# Sheet1.net
KiCad netlist of a schematic drawn in Altium Designer
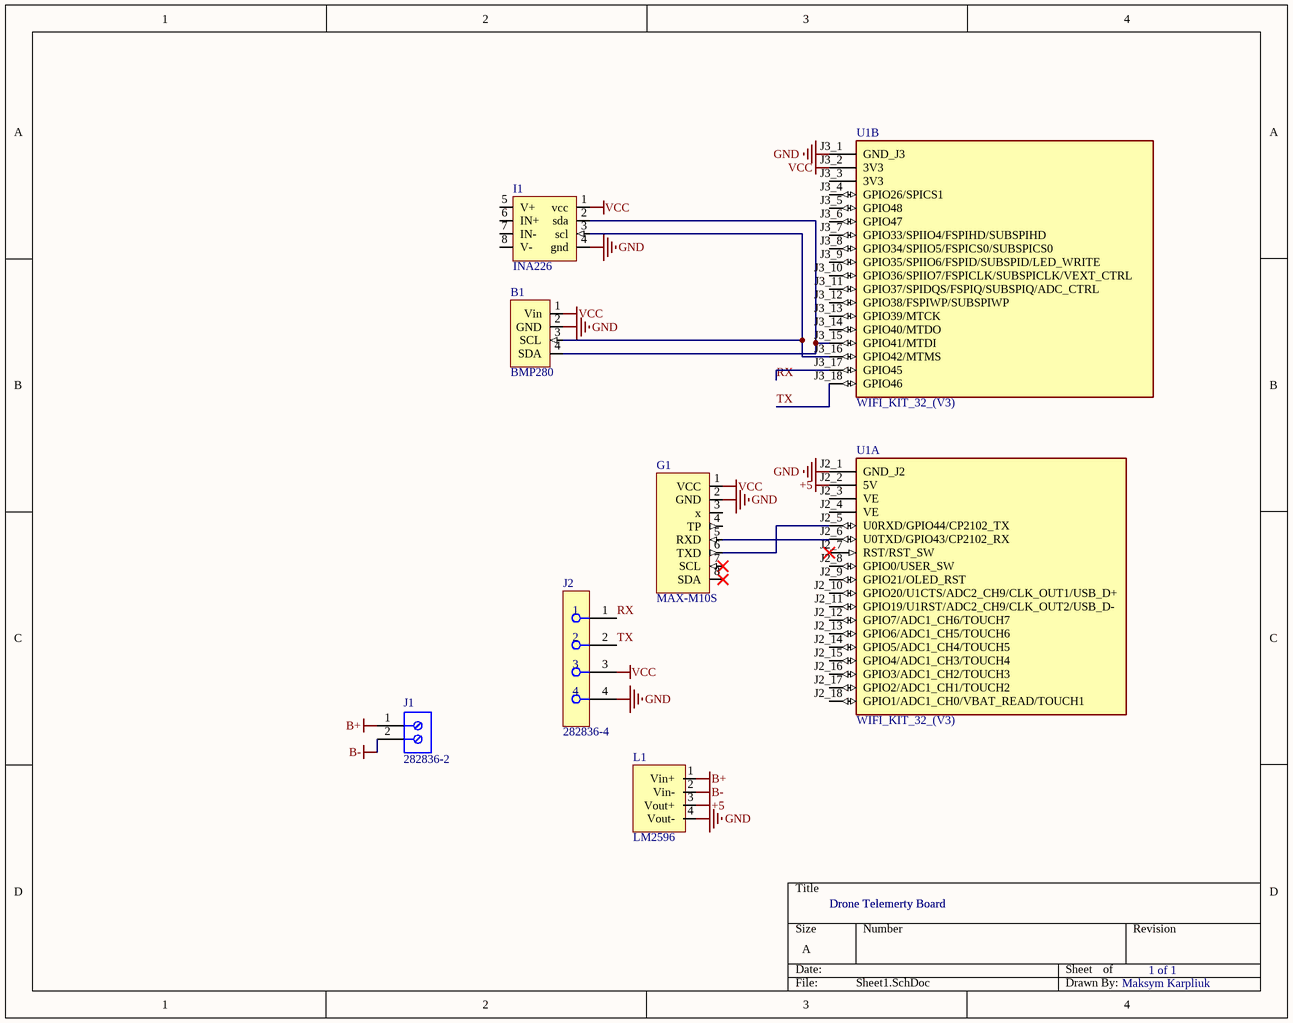
[diagram p0: Sheet1.SchDoc]

(export (version "E")
  (design (tool "Eeschema 10.0.6"))
  (components
    (comp (ref "B1") (value "BMP280") (footprint "BMP280") (libsource (lib "Schlib1") (part "BMP280")))
    (comp (ref "G1") (value "MAX-M10S") (footprint "MAX-M10S") (libsource (lib "Schlib1") (part "MAX-M10S")))
    (comp (ref "I1") (value "INA226") (footprint "INA226") (libsource (lib "Schlib1") (part "INA226")))
    (comp (ref "J1")
      (value "282836-2")
      (footprint "TECO-282836-2_V")
      (description "Female Header, Pitch 5 mm, 1 x 2 Position, Height 10 mm, Tail Length 3.5 mm, Rohs, Bulk")
      (fields (field (name "VOLTAGE") "300V") (field (name "MANUFACTURER") "TE Connectivity"))
      (libsource (lib "Altium Content Vault") (part "CN-1P-F-TB2"))
    )
    (comp (ref "J2")
      (value "282836-4")
      (footprint "FP-282836-4-MFG")
      (description "282836-4 Connector, Terminal Block; Wire Receptacle; 4 Pos.; 16-30 AWG; 0.197 in. CL; Sid")
      (fields (field (name "VOLTAGE") "300V"))
      (libsource (lib "Altium Content Vault") (part "282836-4"))
    )
    (comp (ref "L1") (value "LM2596") (footprint "LM2596") (libsource (lib "Schlib1") (part "LM2596")))
    (comp (ref "U1")
      (value "WIFI_KIT_32_(V3)")
      (footprint "MODULE_WIFI_KIT_32_(V3)")
      (description "*GPIO input only*ADC preamplifier*GPIOs are 3.3V tolerant only")
      (fields (field (name "MF") "Heltec Automation") (field (name "MP") "WIFI KIT 32 (V3)"))
      (libsource (lib "WIFI_KIT_32__V3_") (part "WIFI_KIT_32_(V3)"))
    )
  )
  (nets
    (net (code "1") (name "+5") (class "Default")
      (node (ref "L1") (pin "3") (pinfunction "Vout+_3") (pintype "power_in"))
      (node (ref "U1") (pin "J2_2") (pinfunction "5V_J2_2") (pintype "power_in"))
    )
    (net (code "2") (name "/RX") (class "Default")
      (node (ref "J2") (pin "1") (pinfunction "1_1") (pintype "passive"))
      (node (ref "U1") (pin "J3_17") (pinfunction "GPIO45_J3_17") (pintype "bidirectional"))
    )
    (net (code "3") (name "/TX") (class "Default")
      (node (ref "J2") (pin "2") (pinfunction "2_2") (pintype "passive"))
      (node (ref "U1") (pin "J3_18") (pinfunction "GPIO46_J3_18") (pintype "bidirectional"))
    )
    (net (code "4") (name "B+") (class "Default")
      (node (ref "J1") (pin "1") (pinfunction "1_1") (pintype "passive"))
      (node (ref "L1") (pin "1") (pinfunction "Vin+_1") (pintype "power_in"))
    )
    (net (code "5") (name "B-") (class "Default")
      (node (ref "J1") (pin "2") (pinfunction "2_2") (pintype "passive"))
      (node (ref "L1") (pin "2") (pinfunction "Vin-_2") (pintype "power_in"))
    )
    (net (code "6") (name "GND") (class "Default")
      (node (ref "B1") (pin "2") (pinfunction "GND_2") (pintype "power_in"))
      (node (ref "G1") (pin "2") (pinfunction "GND_2") (pintype "power_in"))
      (node (ref "I1") (pin "4") (pinfunction "gnd_4") (pintype "power_in"))
      (node (ref "J2") (pin "4") (pinfunction "4_4") (pintype "passive"))
      (node (ref "L1") (pin "4") (pinfunction "Vout-_4") (pintype "power_in"))
      (node (ref "U1") (pin "J2_1") (pinfunction "GND_J2_J2_1") (pintype "power_in"))
      (node (ref "U1") (pin "J3_1") (pinfunction "GND_J3_J3_1") (pintype "power_in"))
    )
    (net (code "7") (name "Net-(B1-SCL)") (class "Default")
      (node (ref "B1") (pin "3") (pinfunction "SCL_3") (pintype "input"))
      (node (ref "I1") (pin "3") (pinfunction "scl_3") (pintype "input"))
      (node (ref "U1") (pin "J3_16") (pinfunction "GPIO42/MTMS_J3_16") (pintype "bidirectional"))
    )
    (net (code "8") (name "Net-(B1-SDA)") (class "Default")
      (node (ref "B1") (pin "4") (pinfunction "SDA_4") (pintype "bidirectional"))
      (node (ref "I1") (pin "2") (pinfunction "sda_2") (pintype "bidirectional"))
      (node (ref "U1") (pin "J3_15") (pinfunction "GPIO41/MTDI_J3_15") (pintype "bidirectional"))
    )
    (net (code "9") (name "Net-(G1-RXD)") (class "Default")
      (node (ref "G1") (pin "5") (pinfunction "RXD_5") (pintype "input"))
      (node (ref "U1") (pin "J2_6") (pinfunction "U0TXD/GPIO43/CP2102_RX_J2_6") (pintype "bidirectional"))
    )
    (net (code "10") (name "Net-(G1-TXD)") (class "Default")
      (node (ref "G1") (pin "6") (pinfunction "TXD_6") (pintype "output"))
      (node (ref "U1") (pin "J2_5") (pinfunction "U0RXD/GPIO44/CP2102_TX_J2_5") (pintype "bidirectional"))
    )
    (net (code "11") (name "VCC") (class "Default")
      (node (ref "B1") (pin "1") (pinfunction "Vin_1") (pintype "power_in"))
      (node (ref "G1") (pin "1") (pinfunction "VCC_1") (pintype "power_in"))
      (node (ref "I1") (pin "1") (pinfunction "vcc_1") (pintype "power_in"))
      (node (ref "J2") (pin "3") (pinfunction "3_3") (pintype "passive"))
      (node (ref "U1") (pin "J3_2") (pinfunction "3V3_J3_2") (pintype "power_in"))
    )
    (net (code "12") (name "unconnected-(G1-SCL-Pad7)") (class "Default")
      (node (ref "G1") (pin "7") (pinfunction "SCL_7") (pintype "input+no_connect"))
    )
    (net (code "13") (name "unconnected-(G1-SDA-Pad8)") (class "Default")
      (node (ref "G1") (pin "8") (pinfunction "SDA_8") (pintype "bidirectional+no_connect"))
    )
    (net (code "14") (name "unconnected-(G1-TP-Pad4)") (class "Default")
      (node (ref "G1") (pin "4") (pinfunction "TP_4") (pintype "output"))
    )
    (net (code "15") (name "unconnected-(G1-x-Pad3)") (class "Default")
      (node (ref "G1") (pin "3") (pinfunction "x_3") (pintype "passive"))
    )
    (net (code "16") (name "unconnected-(I1-IN+-Pad6)") (class "Default")
      (node (ref "I1") (pin "6") (pinfunction "IN+_6") (pintype "passive"))
    )
    (net (code "17") (name "unconnected-(I1-IN--Pad7)") (class "Default")
      (node (ref "I1") (pin "7") (pinfunction "IN-_7") (pintype "passive"))
    )
    (net (code "18") (name "unconnected-(I1-V+-Pad5)") (class "Default")
      (node (ref "I1") (pin "5") (pinfunction "V+_5") (pintype "passive"))
    )
    (net (code "19") (name "unconnected-(I1-V--Pad8)") (class "Default")
      (node (ref "I1") (pin "8") (pinfunction "V-_8") (pintype "passive"))
    )
    (net (code "20") (name "unconnected-(U1A-GPIO0{slash}USER_SW-PadJ2_8)") (class "Default")
      (node (ref "U1") (pin "J2_8") (pinfunction "GPIO0/USER_SW_J2_8") (pintype "bidirectional"))
    )
    (net (code "21") (name "unconnected-(U1A-GPIO1{slash}ADC1_CH0{slash}VBAT_READ{slash}TOUCH1-PadJ2_18)") (class "Default")
      (node (ref "U1") (pin "J2_18") (pinfunction "GPIO1/ADC1_CH0/VBAT_READ/TOUCH1_J2_18") (pintype "bidirectional"))
    )
    (net (code "22") (name "unconnected-(U1A-GPIO2{slash}ADC1_CH1{slash}TOUCH2-PadJ2_17)") (class "Default")
      (node (ref "U1") (pin "J2_17") (pinfunction "GPIO2/ADC1_CH1/TOUCH2_J2_17") (pintype "bidirectional"))
    )
    (net (code "23") (name "unconnected-(U1A-GPIO3{slash}ADC1_CH2{slash}TOUCH3-PadJ2_16)") (class "Default")
      (node (ref "U1") (pin "J2_16") (pinfunction "GPIO3/ADC1_CH2/TOUCH3_J2_16") (pintype "bidirectional"))
    )
    (net (code "24") (name "unconnected-(U1A-GPIO4{slash}ADC1_CH3{slash}TOUCH4-PadJ2_15)") (class "Default")
      (node (ref "U1") (pin "J2_15") (pinfunction "GPIO4/ADC1_CH3/TOUCH4_J2_15") (pintype "bidirectional"))
    )
    (net (code "25") (name "unconnected-(U1A-GPIO5{slash}ADC1_CH4{slash}TOUCH5-PadJ2_14)") (class "Default")
      (node (ref "U1") (pin "J2_14") (pinfunction "GPIO5/ADC1_CH4/TOUCH5_J2_14") (pintype "bidirectional"))
    )
    (net (code "26") (name "unconnected-(U1A-GPIO6{slash}ADC1_CH5{slash}TOUCH6-PadJ2_13)") (class "Default")
      (node (ref "U1") (pin "J2_13") (pinfunction "GPIO6/ADC1_CH5/TOUCH6_J2_13") (pintype "bidirectional"))
    )
    (net (code "27") (name "unconnected-(U1A-GPIO7{slash}ADC1_CH6{slash}TOUCH7-PadJ2_12)") (class "Default")
      (node (ref "U1") (pin "J2_12") (pinfunction "GPIO7/ADC1_CH6/TOUCH7_J2_12") (pintype "bidirectional"))
    )
    (net (code "28") (name "unconnected-(U1A-GPIO19{slash}U1RST{slash}ADC2_CH9{slash}CLK_OUT2{slash}USB_D--PadJ2_11)") (class "Default")
      (node (ref "U1") (pin "J2_11") (pinfunction "GPIO19/U1RST/ADC2_CH9/CLK_OUT2/USB_D-_J2_11") (pintype "bidirectional"))
    )
    (net (code "29") (name "unconnected-(U1A-GPIO20{slash}U1CTS{slash}ADC2_CH9{slash}CLK_OUT1{slash}USB_D+-PadJ2_10)") (class "Default")
      (node (ref "U1") (pin "J2_10") (pinfunction "GPIO20/U1CTS/ADC2_CH9/CLK_OUT1/USB_D+_J2_10") (pintype "bidirectional"))
    )
    (net (code "30") (name "unconnected-(U1A-GPIO21{slash}OLED_RST-PadJ2_9)") (class "Default")
      (node (ref "U1") (pin "J2_9") (pinfunction "GPIO21/OLED_RST_J2_9") (pintype "bidirectional"))
    )
    (net (code "31") (name "unconnected-(U1A-RST{slash}RST_SW-PadJ2_7)") (class "Default")
      (node (ref "U1") (pin "J2_7") (pinfunction "RST/RST_SW_J2_7") (pintype "input+no_connect"))
    )
    (net (code "32") (name "unconnected-(U1A-VE-PadJ2_3)") (class "Default")
      (node (ref "U1") (pin "J2_3") (pinfunction "VE_J2_3") (pintype "power_in"))
    )
    (net (code "33") (name "unconnected-(U1A-VE-PadJ2_4)") (class "Default")
      (node (ref "U1") (pin "J2_4") (pinfunction "VE_J2_4") (pintype "power_in"))
    )
    (net (code "34") (name "unconnected-(U1B-3V3-PadJ3_3)") (class "Default")
      (node (ref "U1") (pin "J3_3") (pinfunction "3V3_J3_3") (pintype "power_in"))
    )
    (net (code "35") (name "unconnected-(U1B-GPIO26{slash}SPICS1-PadJ3_4)") (class "Default")
      (node (ref "U1") (pin "J3_4") (pinfunction "GPIO26/SPICS1_J3_4") (pintype "bidirectional"))
    )
    (net (code "36") (name "unconnected-(U1B-GPIO33{slash}SPIIO4{slash}FSPIHD{slash}SUBSPIHD-PadJ3_7)") (class "Default")
      (node (ref "U1") (pin "J3_7") (pinfunction "GPIO33/SPIIO4/FSPIHD/SUBSPIHD_J3_7") (pintype "bidirectional"))
    )
    (net (code "37") (name "unconnected-(U1B-GPIO34{slash}SPIIO5{slash}FSPICS0{slash}SUBSPICS0-PadJ3_8)") (class "Default")
      (node (ref "U1") (pin "J3_8") (pinfunction "GPIO34/SPIIO5/FSPICS0/SUBSPICS0_J3_8") (pintype "bidirectional"))
    )
    (net (code "38") (name "unconnected-(U1B-GPIO35{slash}SPIIO6{slash}FSPID{slash}SUBSPID{slash}LED_WRITE-PadJ3_9)") (class "Default")
      (node (ref "U1") (pin "J3_9") (pinfunction "GPIO35/SPIIO6/FSPID/SUBSPID/LED_WRITE_J3_9") (pintype "bidirectional"))
    )
    (net (code "39") (name "unconnected-(U1B-GPIO36{slash}SPIIO7{slash}FSPICLK{slash}SUBSPICLK{slash}VEXT_CTRL-PadJ3_10)") (class "Default")
      (node (ref "U1") (pin "J3_10") (pinfunction "GPIO36/SPIIO7/FSPICLK/SUBSPICLK/VEXT_CTRL_J3_10") (pintype "bidirectional"))
    )
    (net (code "40") (name "unconnected-(U1B-GPIO37{slash}SPIDQS{slash}FSPIQ{slash}SUBSPIQ{slash}ADC_CTRL-PadJ3_11)") (class "Default")
      (node (ref "U1") (pin "J3_11") (pinfunction "GPIO37/SPIDQS/FSPIQ/SUBSPIQ/ADC_CTRL_J3_11") (pintype "bidirectional"))
    )
    (net (code "41") (name "unconnected-(U1B-GPIO38{slash}FSPIWP{slash}SUBSPIWP-PadJ3_12)") (class "Default")
      (node (ref "U1") (pin "J3_12") (pinfunction "GPIO38/FSPIWP/SUBSPIWP_J3_12") (pintype "bidirectional"))
    )
    (net (code "42") (name "unconnected-(U1B-GPIO39{slash}MTCK-PadJ3_13)") (class "Default")
      (node (ref "U1") (pin "J3_13") (pinfunction "GPIO39/MTCK_J3_13") (pintype "bidirectional"))
    )
    (net (code "43") (name "unconnected-(U1B-GPIO40{slash}MTDO-PadJ3_14)") (class "Default")
      (node (ref "U1") (pin "J3_14") (pinfunction "GPIO40/MTDO_J3_14") (pintype "bidirectional"))
    )
    (net (code "44") (name "unconnected-(U1B-GPIO47-PadJ3_6)") (class "Default")
      (node (ref "U1") (pin "J3_6") (pinfunction "GPIO47_J3_6") (pintype "bidirectional"))
    )
    (net (code "45") (name "unconnected-(U1B-GPIO48-PadJ3_5)") (class "Default")
      (node (ref "U1") (pin "J3_5") (pinfunction "GPIO48_J3_5") (pintype "bidirectional"))
    )
  )
)
